# Motor_Driver_T.net
KiCad netlist of a schematic drawn in EasyEDA Pro
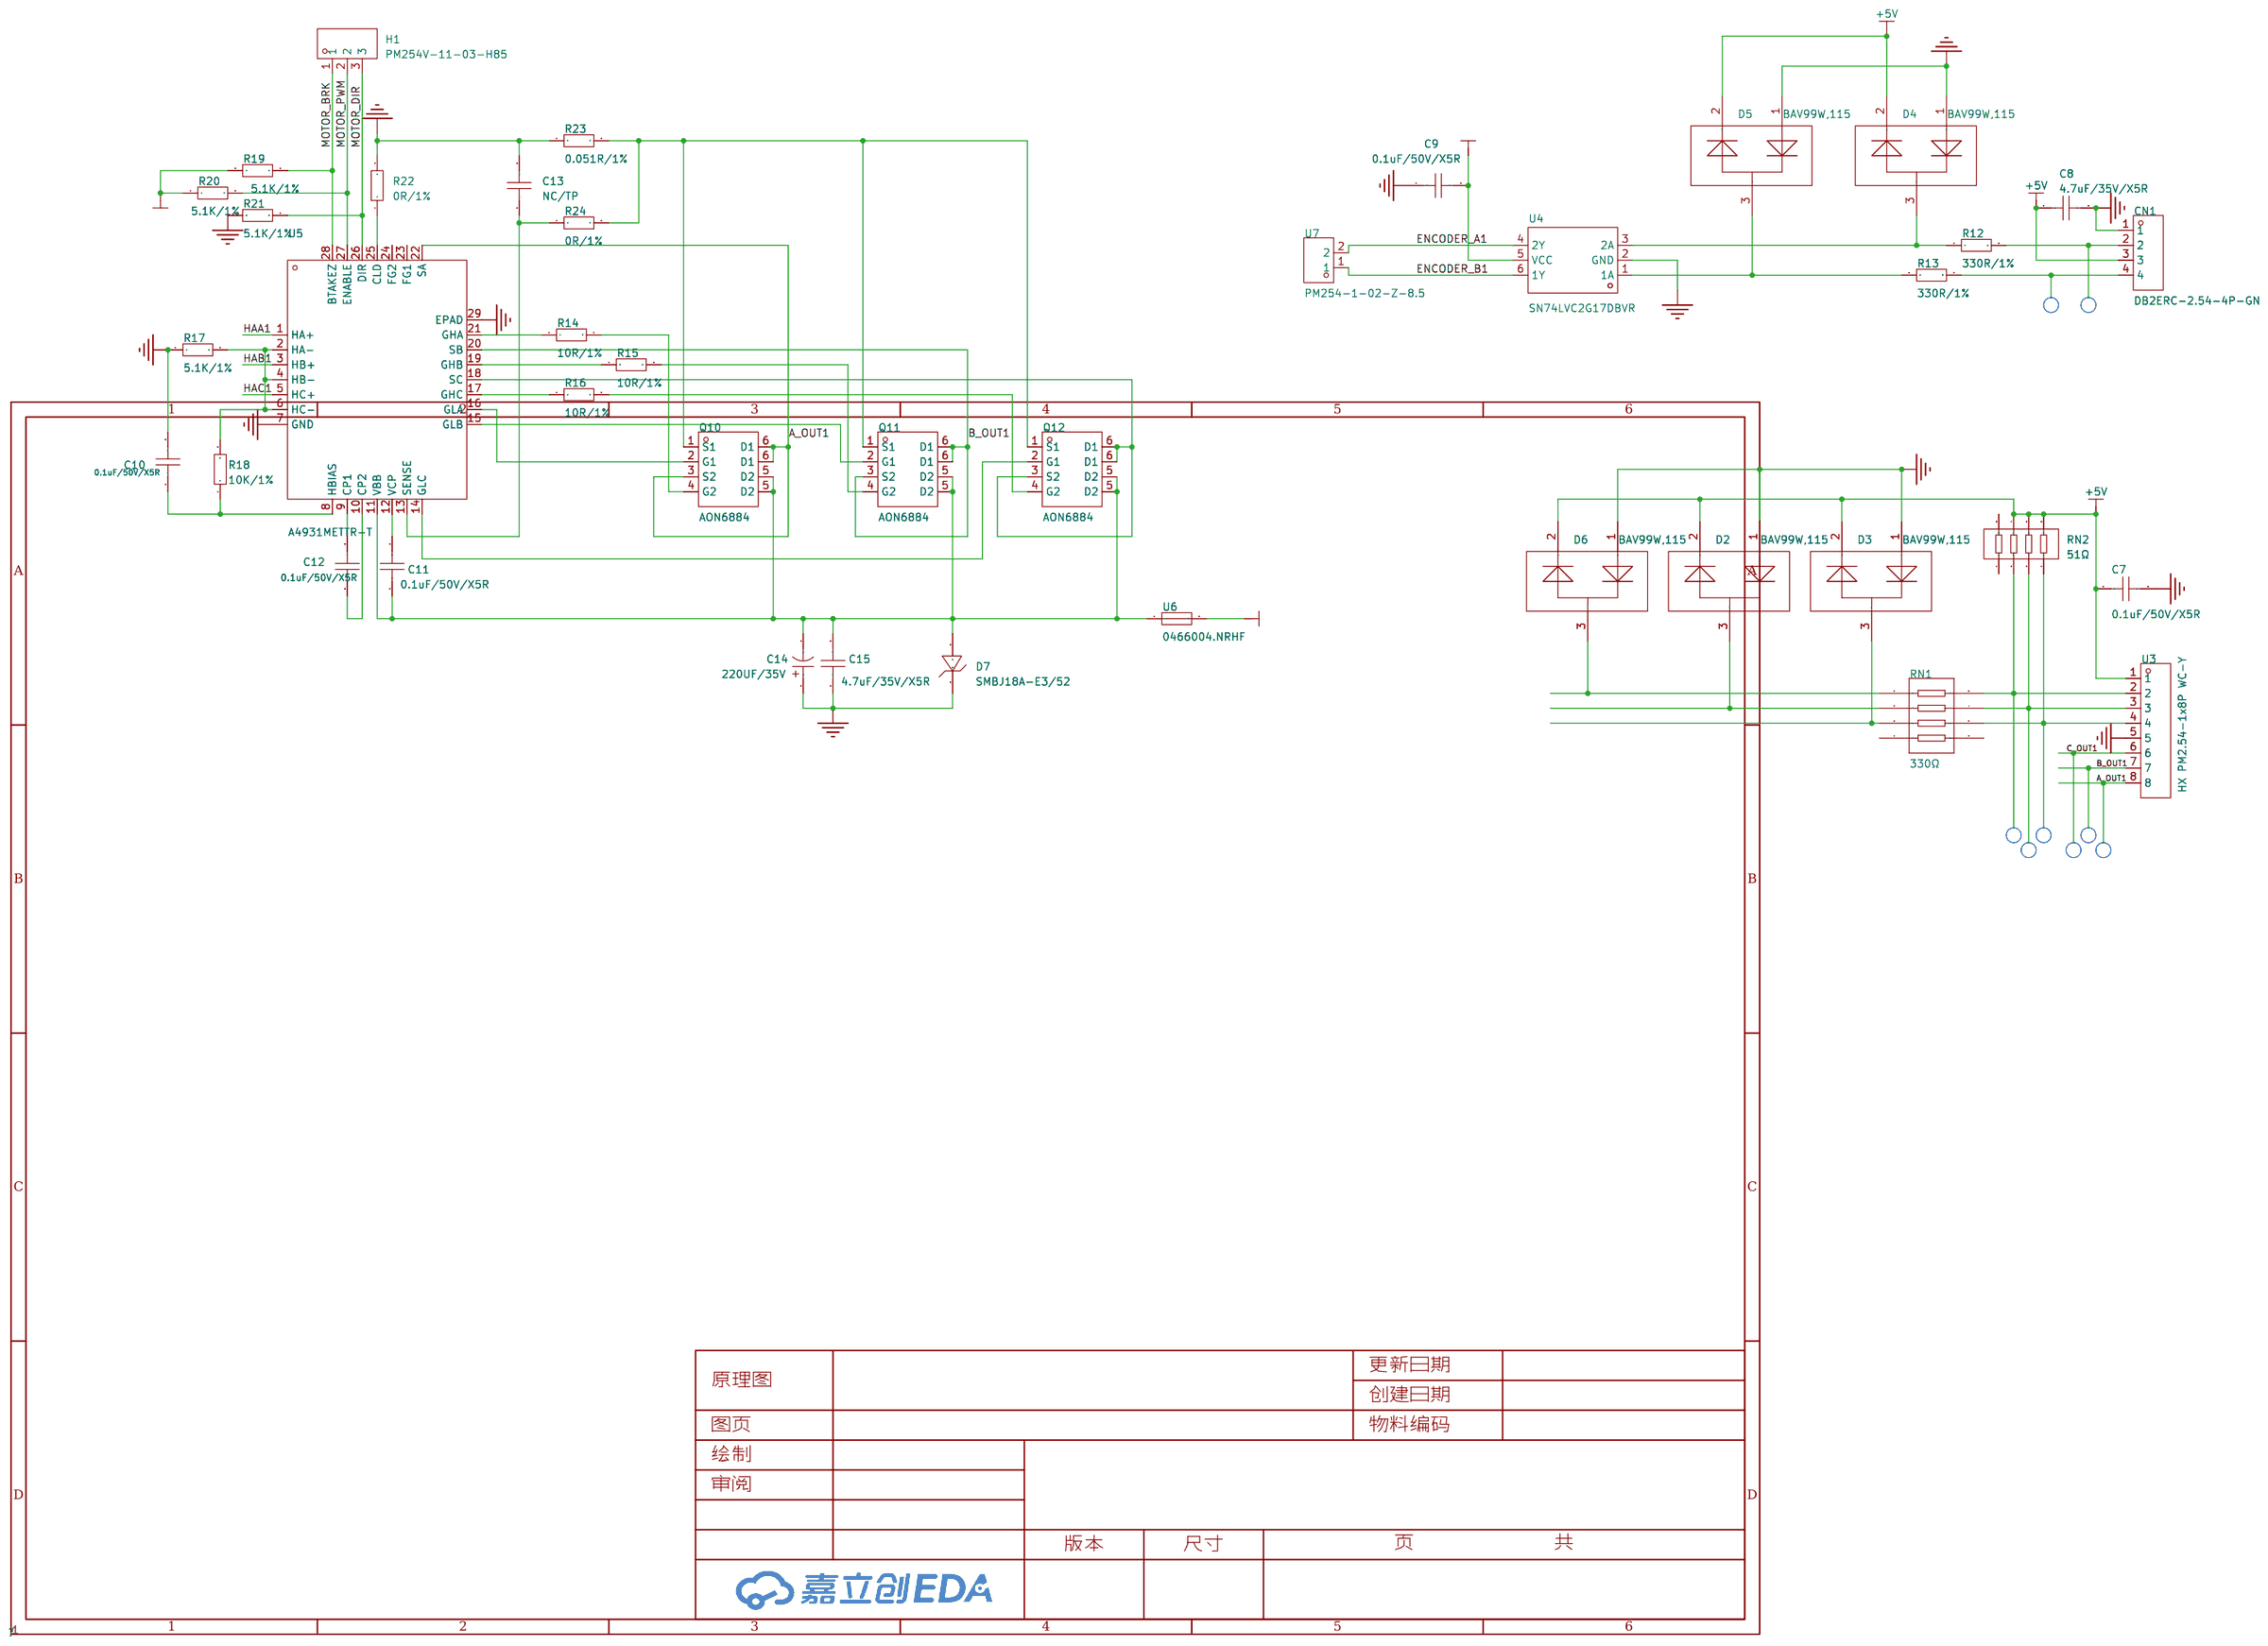
[diagram p0: schematic sheet]

(export (version "E")
  (design (tool "Eeschema 10.0.6"))
  (components
    (comp (ref "C7")
      (value "100nF")
      (footprint "easyedapro:C0603")
      (libsource (lib "easyedapro") (part "CapAcitance"))
    )
    (comp (ref "C8")
      (value "100nF")
      (footprint "easyedapro:C0603")
      (libsource (lib "easyedapro") (part "CapAcitance"))
    )
    (comp (ref "C9")
      (value "100nF")
      (footprint "easyedapro:C0603")
      (libsource (lib "easyedapro") (part "CapAcitance"))
    )
    (comp (ref "C10")
      (value "100nF")
      (footprint "easyedapro:C0603")
      (libsource (lib "easyedapro") (part "CapAcitance"))
    )
    (comp (ref "C11")
      (value "100nF")
      (footprint "easyedapro:C0603")
      (libsource (lib "easyedapro") (part "CapAcitance"))
    )
    (comp (ref "C12")
      (value "100nF")
      (footprint "easyedapro:C0603")
      (libsource (lib "easyedapro") (part "CapAcitance"))
    )
    (comp (ref "C13")
      (value "100nF")
      (footprint "easyedapro:C0603")
      (libsource (lib "easyedapro") (part "CapAcitance"))
    )
    (comp (ref "C14")
      (value "220uF")
      (footprint "easyedapro:CAP-SMD_BD8.0-L8.3-W8.3-LS9.3-FD")
      (description "容值:220uF;精度:±20%;额定电压:35V;纹波电流:195mA@120Hz;等效串联电阻:-;")
      (fields
        (field (name "Manufacturer Part") "RVT220UF35V67RV0024")
        (field (name "Manufacturer") "KNSCHA(科尼盛)")
      )
      (libsource (lib "easyedapro") (part "RVT220UF35V67RV0024"))
    )
    (comp (ref "C15")
      (value "100nF")
      (footprint "easyedapro:C0603")
      (libsource (lib "easyedapro") (part "CapAcitance"))
    )
    (comp (ref "CN1")
      (value "DB2ERC-2.54-4P-GN")
      (footprint "easyedapro:CONN-TH_4P-P2.54_DIBO_DB2ERC-2.54-4P-GN")
      (fields (field (name "Manufacturer") "DORABO(地博电气)"))
      (libsource (lib "easyedapro") (part "DB2ERC-2.54-4P-GN"))
    )
    (comp (ref "D2")
      (value "BAV99W,115")
      (footprint "easyedapro:SOT-323_L2.0-W1.3-P1.30-LS2.1-BR")
      (description "二极管配置:1对串联式;正向压降(Vf):1.25V@150mA;直流反向耐压(Vr):100V;平均整流电流(Io):150mA;功率:200mW;反向恢复时间(trr):4ns;")
      (fields (field (name "Manufacturer") "Nexperia(安世)"))
      (libsource (lib "easyedapro") (part "BAV99W,115"))
    )
    (comp (ref "D3")
      (value "BAV99W,115")
      (footprint "easyedapro:SOT-323_L2.0-W1.3-P1.30-LS2.1-BR")
      (description "二极管配置:1对串联式;正向压降(Vf):1.25V@150mA;直流反向耐压(Vr):100V;平均整流电流(Io):150mA;功率:200mW;反向恢复时间(trr):4ns;")
      (fields (field (name "Manufacturer") "Nexperia(安世)"))
      (libsource (lib "easyedapro") (part "BAV99W,115"))
    )
    (comp (ref "D4")
      (value "BAV99W,115")
      (footprint "easyedapro:SOT-323_L2.0-W1.3-P1.30-LS2.1-BR")
      (description "二极管配置:1对串联式;正向压降(Vf):1.25V@150mA;直流反向耐压(Vr):100V;平均整流电流(Io):150mA;功率:200mW;反向恢复时间(trr):4ns;")
      (fields (field (name "Manufacturer") "Nexperia(安世)"))
      (libsource (lib "easyedapro") (part "BAV99W,115"))
    )
    (comp (ref "D5")
      (value "BAV99W,115")
      (footprint "easyedapro:SOT-323_L2.0-W1.3-P1.30-LS2.1-BR")
      (description "二极管配置:1对串联式;正向压降(Vf):1.25V@150mA;直流反向耐压(Vr):100V;平均整流电流(Io):150mA;功率:200mW;反向恢复时间(trr):4ns;")
      (fields (field (name "Manufacturer") "Nexperia(安世)"))
      (libsource (lib "easyedapro") (part "BAV99W,115"))
    )
    (comp (ref "D6")
      (value "BAV99W,115")
      (footprint "easyedapro:SOT-323_L2.0-W1.3-P1.30-LS2.1-BR")
      (description "二极管配置:1对串联式;正向压降(Vf):1.25V@150mA;直流反向耐压(Vr):100V;平均整流电流(Io):150mA;功率:200mW;反向恢复时间(trr):4ns;")
      (fields (field (name "Manufacturer") "Nexperia(安世)"))
      (libsource (lib "easyedapro") (part "BAV99W,115"))
    )
    (comp (ref "D7")
      (value "SMBJ18A-E3/52")
      (footprint "easyedapro:SMB_L4.6-W3.6-LS5.4-RD")
      (description "反向截止电压(Vrwm):18V;最大钳位电压:29.2V;峰值脉冲电流(Ipp)@10/1000us:20.5A;峰值脉冲功率(Ppp)@10/1000us:600W;击穿电压:20V;")
      (fields (field (name "Manufacturer") "VISHAY(威世)"))
      (libsource (lib "easyedapro") (part "SMBJ18A-E3/52"))
    )
    (comp (ref "H1")
      (value "PM254V-11-03-H85")
      (footprint "easyedapro:HDR-TH_3P-P2.54-V-F")
      (description "插孔结构:1x3P;间距:2.54mm;行距:-;安装类型:直插;排数:单排;总孔位数:3P;塑高:-;触头材质:黄铜;触头镀层:-;")
      (fields (field (name "Manufacturer") "XFCN(兴飞)"))
      (libsource (lib "easyedapro") (part "PM254V-11-03-H85"))
    )
    (comp (ref "Q10")
      (value "AON6884")
      (footprint "easyedapro:DFN-8_L5.5-W5.2-P1.27-LS6.0-BL-EP2")
      (fields (field (name "Manufacturer") "AOS"))
      (libsource (lib "easyedapro") (part "AON6884"))
    )
    (comp (ref "Q11")
      (value "AON6884")
      (footprint "easyedapro:DFN-8_L5.5-W5.2-P1.27-LS6.0-BL-EP2")
      (fields (field (name "Manufacturer") "AOS"))
      (libsource (lib "easyedapro") (part "AON6884"))
    )
    (comp (ref "Q12")
      (value "AON6884")
      (footprint "easyedapro:DFN-8_L5.5-W5.2-P1.27-LS6.0-BL-EP2")
      (fields (field (name "Manufacturer") "AOS"))
      (libsource (lib "easyedapro") (part "AON6884"))
    )
    (comp (ref "R12") (value "10K") (footprint "easyedapro:R0603") (libsource (lib "easyedapro") (part "电阻")))
    (comp (ref "R13") (value "10K") (footprint "easyedapro:R0603") (libsource (lib "easyedapro") (part "电阻")))
    (comp (ref "R14") (value "10K") (footprint "easyedapro:R0603") (libsource (lib "easyedapro") (part "电阻")))
    (comp (ref "R15") (value "10K") (footprint "easyedapro:R0603") (libsource (lib "easyedapro") (part "电阻")))
    (comp (ref "R16") (value "10K") (footprint "easyedapro:R0603") (libsource (lib "easyedapro") (part "电阻")))
    (comp (ref "R17") (value "10K") (footprint "easyedapro:R0603") (libsource (lib "easyedapro") (part "电阻")))
    (comp (ref "R18")
      (value "10K/1%")
      (footprint "easyedapro:R0603")
      (libsource (lib "easyedapro") (part "电阻"))
    )
    (comp (ref "R19") (value "10K") (footprint "easyedapro:R0603") (libsource (lib "easyedapro") (part "电阻")))
    (comp (ref "R20") (value "10K") (footprint "easyedapro:R0603") (libsource (lib "easyedapro") (part "电阻")))
    (comp (ref "R21") (value "10K") (footprint "easyedapro:R0603") (libsource (lib "easyedapro") (part "电阻")))
    (comp (ref "R22") (value "10K") (footprint "easyedapro:R0603") (libsource (lib "easyedapro") (part "电阻")))
    (comp (ref "R23") (value "10K") (footprint "easyedapro:R0603") (libsource (lib "easyedapro") (part "电阻")))
    (comp (ref "R24") (value "10K") (footprint "easyedapro:R0603") (libsource (lib "easyedapro") (part "电阻")))
    (comp (ref "RN1")
      (value "330Ω")
      (footprint "easyedapro:RES-ARRAY-SMD_0603-8P-L3.2-W1.6-BL")
      (description "电阻器数:4;阻值:330Ω;精度:±5%;单个元件功率:62.5mW;温度系数:±200ppm/°C;")
      (fields
        (field (name "Manufacturer Part") "4D03WGJ0331T5E")
        (field (name "Manufacturer") "UNI-ROYAL(厚声)")
      )
      (libsource (lib "easyedapro") (part "4D03WGJ0331T5E"))
    )
    (comp (ref "RN2")
      (value "51Ω")
      (footprint "easyedapro:RES-ARRAY-SMD_8P-L3.2-W1.6-P0.80-BL-1")
      (description "电阻器数:4;阻值:51Ω;精度:±5%;单个元件功率:62.5mW;温度系数:±200ppm/°C;")
      (fields (field (name "Manufacturer Part") "YC164-JR-0751RL") (field (name "Manufacturer") "YAGEO(国巨)"))
      (libsource (lib "easyedapro") (part "YC164-JR-0751RL"))
    )
    (comp (ref "U3")
      (value "HX PM2.54-1x8P WC-Y")
      (footprint "easyedapro:HDR-TH_8P-P2.54-H-F-W10.3-N")
      (fields (field (name "Manufacturer") "hanxia(韩下)"))
      (libsource (lib "easyedapro") (part "HX PM2.54-1X8P WC-Y"))
    )
    (comp (ref "U4")
      (value "SN74LVC2G17DBVR")
      (footprint "easyedapro:SOT-23-6_L2.9-W1.6-P0.95-LS2.8-BL")
      (description "输入类型:施密特触发器;电源电压:1.65V~5.5V;元件数:2;每个元件位数:1;灌电流(IOL):32mA;拉电流(IOH):32mA;")
      (fields (field (name "Manufacturer") "TI(德州仪器)"))
      (libsource (lib "easyedapro") (part "SN74LVC2G17DBVR"))
    )
    (comp (ref "U5")
      (value "A4931METTR-T")
      (footprint "easyedapro:WQFN-28_L5.0-W5.0-P0.50-BL-EP3.2")
      (description "微功率，超灵敏，霍尔开关")
      (fields (field (name "Manufacturer") "ALLEGRO(美国埃戈罗)"))
      (libsource (lib "easyedapro") (part "A4931METTR-T"))
    )
    (comp (ref "U6")
      (value "0466004.NRHF")
      (footprint "easyedapro:F1206")
      (description "类型:贴片式保险丝;额定电流:4A;额定电压 (AC):32V;额定电压 (DC):32V;分断能力:50A;")
      (fields (field (name "Manufacturer") "Littelfuse(美国力特)"))
      (libsource (lib "easyedapro") (part "0466004.NRHF"))
    )
    (comp (ref "U7")
      (value "PM254-1-02-Z-8.5")
      (footprint "easyedapro:HDR-TH_2P-P2.54-V-F")
      (fields (field (name "Manufacturer") "HCTL(华灿天禄)"))
      (libsource (lib "easyedapro") (part "PM254-1-02-Z-8.5"))
    )
  )
  (nets
    (net (code "1") (name "+3V3") (class "Default")
      (node (ref "C9") (pin "2") (pinfunction "2_2") (pintype "input"))
      (node (ref "R19") (pin "1") (pinfunction "1_1") (pintype "input"))
      (node (ref "R20") (pin "1") (pinfunction "1_1") (pintype "input"))
      (node (ref "U4") (pin "5") (pinfunction "VCC_5") (pintype "unspecified"))
    )
    (net (code "2") (name "+5V") (class "Default")
      (node (ref "C7") (pin "1") (pinfunction "1_1") (pintype "input"))
      (node (ref "C8") (pin "1") (pinfunction "1_1") (pintype "input"))
      (node (ref "CN1") (pin "3") (pinfunction "3_3") (pintype "unspecified"))
      (node (ref "D2") (pin "2") (pinfunction "2_2") (pintype "input"))
      (node (ref "D3") (pin "2") (pinfunction "2_2") (pintype "input"))
      (node (ref "D4") (pin "2") (pinfunction "2_2") (pintype "input"))
      (node (ref "D5") (pin "2") (pinfunction "2_2") (pintype "input"))
      (node (ref "D6") (pin "2") (pinfunction "2_2") (pintype "input"))
      (node (ref "RN2") (pin "5") (pinfunction "5_5") (pintype "input"))
      (node (ref "RN2") (pin "6") (pinfunction "6_6") (pintype "input"))
      (node (ref "RN2") (pin "7") (pinfunction "7_7") (pintype "input"))
      (node (ref "U3") (pin "1") (pinfunction "1_1") (pintype "unspecified"))
    )
    (net (code "3") (name "/A_OUT1") (class "Default")
      (node (ref "Q10") (pin "3") (pinfunction "S2_3") (pintype "unspecified"))
      (node (ref "Q10") (pin "6") (pinfunction "D1_6") (pintype "unspecified"))
      (node (ref "U3") (pin "8") (pinfunction "8_8") (pintype "unspecified"))
      (node (ref "U5") (pin "22") (pinfunction "SA_22") (pintype "unspecified"))
    )
    (net (code "4") (name "/B_OUT1") (class "Default")
      (node (ref "Q11") (pin "3") (pinfunction "S2_3") (pintype "unspecified"))
      (node (ref "Q11") (pin "6") (pinfunction "D1_6") (pintype "unspecified"))
      (node (ref "U3") (pin "7") (pinfunction "7_7") (pintype "unspecified"))
      (node (ref "U5") (pin "20") (pinfunction "SB_20") (pintype "unspecified"))
    )
    (net (code "5") (name "/C_OUT1") (class "Default")
      (node (ref "U3") (pin "6") (pinfunction "6_6") (pintype "unspecified"))
    )
    (net (code "6") (name "/ENCODER_A1") (class "Default")
      (node (ref "U4") (pin "4") (pinfunction "2Y_4") (pintype "unspecified"))
      (node (ref "U7") (pin "2") (pinfunction "2_2") (pintype "unspecified"))
    )
    (net (code "7") (name "/ENCODER_B1") (class "Default")
      (node (ref "U4") (pin "6") (pinfunction "1Y_6") (pintype "unspecified"))
      (node (ref "U7") (pin "1") (pinfunction "1_1") (pintype "unspecified"))
    )
    (net (code "8") (name "/HAA1") (class "Default")
      (node (ref "U5") (pin "1") (pinfunction "HA+_1") (pintype "unspecified"))
    )
    (net (code "9") (name "/HAB1") (class "Default")
      (node (ref "U5") (pin "3") (pinfunction "HB+_3") (pintype "unspecified"))
    )
    (net (code "10") (name "/HAC1") (class "Default")
      (node (ref "U5") (pin "5") (pinfunction "HC+_5") (pintype "unspecified"))
    )
    (net (code "11") (name "/MOTOR_BRK") (class "Default")
      (node (ref "H1") (pin "1") (pinfunction "1_1") (pintype "unspecified"))
      (node (ref "R19") (pin "2") (pinfunction "2_2") (pintype "input"))
      (node (ref "U5") (pin "28") (pinfunction "BTAKEZ_28") (pintype "unspecified"))
    )
    (net (code "12") (name "/MOTOR_DIR") (class "Default")
      (node (ref "H1") (pin "3") (pinfunction "3_3") (pintype "unspecified"))
      (node (ref "R21") (pin "2") (pinfunction "2_2") (pintype "input"))
      (node (ref "U5") (pin "26") (pinfunction "DIR_26") (pintype "unspecified"))
    )
    (net (code "13") (name "/MOTOR_PWM") (class "Default")
      (node (ref "H1") (pin "2") (pinfunction "2_2") (pintype "unspecified"))
      (node (ref "R20") (pin "2") (pinfunction "2_2") (pintype "input"))
      (node (ref "U5") (pin "27") (pinfunction "ENABLE_27") (pintype "unspecified"))
    )
    (net (code "14") (name "GND") (class "Default")
      (node (ref "C10") (pin "2") (pinfunction "2_2") (pintype "input"))
      (node (ref "C13") (pin "2") (pinfunction "2_2") (pintype "input"))
      (node (ref "C14") (pin "1") (pinfunction "1_1") (pintype "input"))
      (node (ref "C15") (pin "1") (pinfunction "1_1") (pintype "input"))
      (node (ref "C7") (pin "2") (pinfunction "2_2") (pintype "input"))
      (node (ref "C8") (pin "2") (pinfunction "2_2") (pintype "input"))
      (node (ref "C9") (pin "1") (pinfunction "1_1") (pintype "input"))
      (node (ref "CN1") (pin "1") (pinfunction "1_1") (pintype "unspecified"))
      (node (ref "D2") (pin "1") (pinfunction "1_1") (pintype "input"))
      (node (ref "D3") (pin "1") (pinfunction "1_1") (pintype "input"))
      (node (ref "D4") (pin "1") (pinfunction "1_1") (pintype "input"))
      (node (ref "D5") (pin "1") (pinfunction "1_1") (pintype "input"))
      (node (ref "D6") (pin "1") (pinfunction "1_1") (pintype "input"))
      (node (ref "D7") (pin "1") (pinfunction "C_1") (pintype "input"))
      (node (ref "R17") (pin "1") (pinfunction "1_1") (pintype "input"))
      (node (ref "R21") (pin "1") (pinfunction "1_1") (pintype "input"))
      (node (ref "R22") (pin "2") (pinfunction "2_2") (pintype "input"))
      (node (ref "R23") (pin "1") (pinfunction "1_1") (pintype "input"))
      (node (ref "U3") (pin "5") (pinfunction "5_5") (pintype "unspecified"))
      (node (ref "U4") (pin "2") (pinfunction "GND_2") (pintype "unspecified"))
      (node (ref "U5") (pin "29") (pinfunction "EPAD_29") (pintype "unspecified"))
      (node (ref "U5") (pin "7") (pinfunction "GND_7") (pintype "unspecified"))
    )
    (net (code "15") (name "Net-(CN1-Pad2)") (class "Default")
      (node (ref "CN1") (pin "2") (pinfunction "2_2") (pintype "unspecified"))
      (node (ref "R12") (pin "2") (pinfunction "2_2") (pintype "input"))
    )
    (net (code "16") (name "Net-(CN1-Pad4)") (class "Default")
      (node (ref "CN1") (pin "4") (pinfunction "4_4") (pintype "unspecified"))
      (node (ref "R13") (pin "2") (pinfunction "2_2") (pintype "input"))
    )
    (net (code "17") (name "Net-(D2-Pad3)") (class "Default")
      (node (ref "D2") (pin "3") (pinfunction "3_3") (pintype "input"))
      (node (ref "RN1") (pin "2") (pinfunction "2_2") (pintype "input"))
    )
    (net (code "18") (name "Net-(D3-Pad3)") (class "Default")
      (node (ref "D3") (pin "3") (pinfunction "3_3") (pintype "input"))
      (node (ref "RN1") (pin "3") (pinfunction "3_3") (pintype "input"))
    )
    (net (code "19") (name "Net-(D6-Pad3)") (class "Default")
      (node (ref "D6") (pin "3") (pinfunction "3_3") (pintype "input"))
      (node (ref "RN1") (pin "1") (pinfunction "1_1") (pintype "input"))
    )
    (net (code "20") (name "Net-(D7-A)") (class "Default")
      (node (ref "C11") (pin "1") (pinfunction "1_1") (pintype "input"))
      (node (ref "C14") (pin "2") (pinfunction "2_2") (pintype "input"))
      (node (ref "C15") (pin "2") (pinfunction "2_2") (pintype "input"))
      (node (ref "D7") (pin "2") (pinfunction "A_2") (pintype "input"))
      (node (ref "Q10") (pin "5") (pinfunction "D2_5") (pintype "unspecified"))
      (node (ref "Q11") (pin "5") (pinfunction "D2_5") (pintype "unspecified"))
      (node (ref "Q12") (pin "5") (pinfunction "D2_5") (pintype "unspecified"))
      (node (ref "U5") (pin "11") (pinfunction "VBB_11") (pintype "unspecified"))
      (node (ref "U6") (pin "1") (pinfunction "1_1") (pintype "input"))
    )
    (net (code "21") (name "Net-(Q10-G1)") (class "Default")
      (node (ref "Q10") (pin "2") (pinfunction "G1_2") (pintype "unspecified"))
      (node (ref "U5") (pin "16") (pinfunction "GLA_16") (pintype "unspecified"))
    )
    (net (code "22") (name "Net-(Q10-G2)") (class "Default")
      (node (ref "Q10") (pin "4") (pinfunction "G2_4") (pintype "unspecified"))
      (node (ref "R14") (pin "2") (pinfunction "2_2") (pintype "input"))
    )
    (net (code "23") (name "Net-(Q10-S1)") (class "Default")
      (node (ref "Q10") (pin "1") (pinfunction "S1_1") (pintype "unspecified"))
      (node (ref "Q11") (pin "1") (pinfunction "S1_1") (pintype "unspecified"))
      (node (ref "Q12") (pin "1") (pinfunction "S1_1") (pintype "unspecified"))
      (node (ref "R23") (pin "2") (pinfunction "2_2") (pintype "input"))
      (node (ref "R24") (pin "2") (pinfunction "2_2") (pintype "input"))
    )
    (net (code "24") (name "Net-(Q11-G1)") (class "Default")
      (node (ref "Q11") (pin "2") (pinfunction "G1_2") (pintype "unspecified"))
      (node (ref "U5") (pin "15") (pinfunction "GLB_15") (pintype "unspecified"))
    )
    (net (code "25") (name "Net-(Q11-G2)") (class "Default")
      (node (ref "Q11") (pin "4") (pinfunction "G2_4") (pintype "unspecified"))
      (node (ref "R15") (pin "2") (pinfunction "2_2") (pintype "input"))
    )
    (net (code "26") (name "Net-(Q12-D1)") (class "Default")
      (node (ref "Q12") (pin "3") (pinfunction "S2_3") (pintype "unspecified"))
      (node (ref "Q12") (pin "6") (pinfunction "D1_6") (pintype "unspecified"))
      (node (ref "U5") (pin "18") (pinfunction "SC_18") (pintype "unspecified"))
    )
    (net (code "27") (name "Net-(Q12-G1)") (class "Default")
      (node (ref "Q12") (pin "2") (pinfunction "G1_2") (pintype "unspecified"))
      (node (ref "U5") (pin "14") (pinfunction "GLC_14") (pintype "unspecified"))
    )
    (net (code "28") (name "Net-(Q12-G2)") (class "Default")
      (node (ref "Q12") (pin "4") (pinfunction "G2_4") (pintype "unspecified"))
      (node (ref "R16") (pin "2") (pinfunction "2_2") (pintype "input"))
    )
    (net (code "29") (name "Net-(RN1-Pad6)") (class "Default")
      (node (ref "RN1") (pin "6") (pinfunction "6_6") (pintype "input"))
      (node (ref "RN2") (pin "4") (pinfunction "4_4") (pintype "input"))
      (node (ref "U3") (pin "4") (pinfunction "4_4") (pintype "unspecified"))
    )
    (net (code "30") (name "Net-(RN1-Pad7)") (class "Default")
      (node (ref "RN1") (pin "7") (pinfunction "7_7") (pintype "input"))
      (node (ref "RN2") (pin "3") (pinfunction "3_3") (pintype "input"))
      (node (ref "U3") (pin "3") (pinfunction "3_3") (pintype "unspecified"))
    )
    (net (code "31") (name "Net-(RN1-Pad8)") (class "Default")
      (node (ref "RN1") (pin "8") (pinfunction "8_8") (pintype "input"))
      (node (ref "RN2") (pin "2") (pinfunction "2_2") (pintype "input"))
      (node (ref "U3") (pin "2") (pinfunction "2_2") (pintype "unspecified"))
    )
    (net (code "32") (name "Net-(U4-1A)") (class "Default")
      (node (ref "D5") (pin "3") (pinfunction "3_3") (pintype "input"))
      (node (ref "R13") (pin "1") (pinfunction "1_1") (pintype "input"))
      (node (ref "U4") (pin "1") (pinfunction "1A_1") (pintype "unspecified"))
    )
    (net (code "33") (name "Net-(U4-2A)") (class "Default")
      (node (ref "D4") (pin "3") (pinfunction "3_3") (pintype "input"))
      (node (ref "R12") (pin "1") (pinfunction "1_1") (pintype "input"))
      (node (ref "U4") (pin "3") (pinfunction "2A_3") (pintype "unspecified"))
    )
    (net (code "34") (name "Net-(U5-CLD)") (class "Default")
      (node (ref "R22") (pin "1") (pinfunction "1_1") (pintype "input"))
      (node (ref "U5") (pin "25") (pinfunction "CLD_25") (pintype "unspecified"))
    )
    (net (code "35") (name "Net-(U5-CP1)") (class "Default")
      (node (ref "C12") (pin "1") (pinfunction "1_1") (pintype "input"))
      (node (ref "U5") (pin "9") (pinfunction "CP1_9") (pintype "unspecified"))
    )
    (net (code "36") (name "Net-(U5-CP2)") (class "Default")
      (node (ref "C12") (pin "2") (pinfunction "2_2") (pintype "input"))
      (node (ref "U5") (pin "10") (pinfunction "CP2_10") (pintype "unspecified"))
    )
    (net (code "37") (name "Net-(U5-GHA)") (class "Default")
      (node (ref "R14") (pin "1") (pinfunction "1_1") (pintype "input"))
      (node (ref "U5") (pin "21") (pinfunction "GHA_21") (pintype "unspecified"))
    )
    (net (code "38") (name "Net-(U5-GHB)") (class "Default")
      (node (ref "R15") (pin "1") (pinfunction "1_1") (pintype "input"))
      (node (ref "U5") (pin "19") (pinfunction "GHB_19") (pintype "unspecified"))
    )
    (net (code "39") (name "Net-(U5-GHC)") (class "Default")
      (node (ref "R16") (pin "1") (pinfunction "1_1") (pintype "input"))
      (node (ref "U5") (pin "17") (pinfunction "GHC_17") (pintype "unspecified"))
    )
    (net (code "40") (name "Net-(U5-HA-)") (class "Default")
      (node (ref "R17") (pin "2") (pinfunction "2_2") (pintype "input"))
      (node (ref "R18") (pin "2") (pinfunction "2_2") (pintype "input"))
      (node (ref "U5") (pin "2") (pinfunction "HA-_2") (pintype "unspecified"))
      (node (ref "U5") (pin "4") (pinfunction "HB-_4") (pintype "unspecified"))
      (node (ref "U5") (pin "6") (pinfunction "HC-_6") (pintype "unspecified"))
    )
    (net (code "41") (name "Net-(U5-HBIAS)") (class "Default")
      (node (ref "C10") (pin "1") (pinfunction "1_1") (pintype "input"))
      (node (ref "R18") (pin "1") (pinfunction "1_1") (pintype "input"))
      (node (ref "U5") (pin "8") (pinfunction "HBIAS_8") (pintype "unspecified"))
    )
    (net (code "42") (name "Net-(U5-SENSE)") (class "Default")
      (node (ref "C13") (pin "1") (pinfunction "1_1") (pintype "input"))
      (node (ref "R24") (pin "1") (pinfunction "1_1") (pintype "input"))
      (node (ref "U5") (pin "13") (pinfunction "SENSE_13") (pintype "unspecified"))
    )
    (net (code "43") (name "Net-(U5-VCP)") (class "Default")
      (node (ref "C11") (pin "2") (pinfunction "2_2") (pintype "input"))
      (node (ref "U5") (pin "12") (pinfunction "VCP_12") (pintype "unspecified"))
    )
    (net (code "44") (name "VBAT") (class "Default")
      (node (ref "U6") (pin "2") (pinfunction "2_2") (pintype "input"))
    )
    (net (code "45") (name "unconnected-(RN1-Pad4)") (class "Default")
      (node (ref "RN1") (pin "4") (pinfunction "4_4") (pintype "input"))
    )
    (net (code "46") (name "unconnected-(RN1-Pad5)") (class "Default")
      (node (ref "RN1") (pin "5") (pinfunction "5_5") (pintype "input"))
    )
    (net (code "47") (name "unconnected-(RN2-Pad1)") (class "Default")
      (node (ref "RN2") (pin "1") (pinfunction "1_1") (pintype "input"))
    )
    (net (code "48") (name "unconnected-(RN2-Pad8)") (class "Default")
      (node (ref "RN2") (pin "8") (pinfunction "8_8") (pintype "input"))
    )
    (net (code "49") (name "unconnected-(U5-FG1-Pad23)") (class "Default")
      (node (ref "U5") (pin "23") (pinfunction "FG1_23") (pintype "unspecified"))
    )
    (net (code "50") (name "unconnected-(U5-FG2-Pad24)") (class "Default")
      (node (ref "U5") (pin "24") (pinfunction "FG2_24") (pintype "unspecified"))
    )
  )
)
